# Schema_antenne.net
KiCad netlist of a schematic drawn in Altium Designer
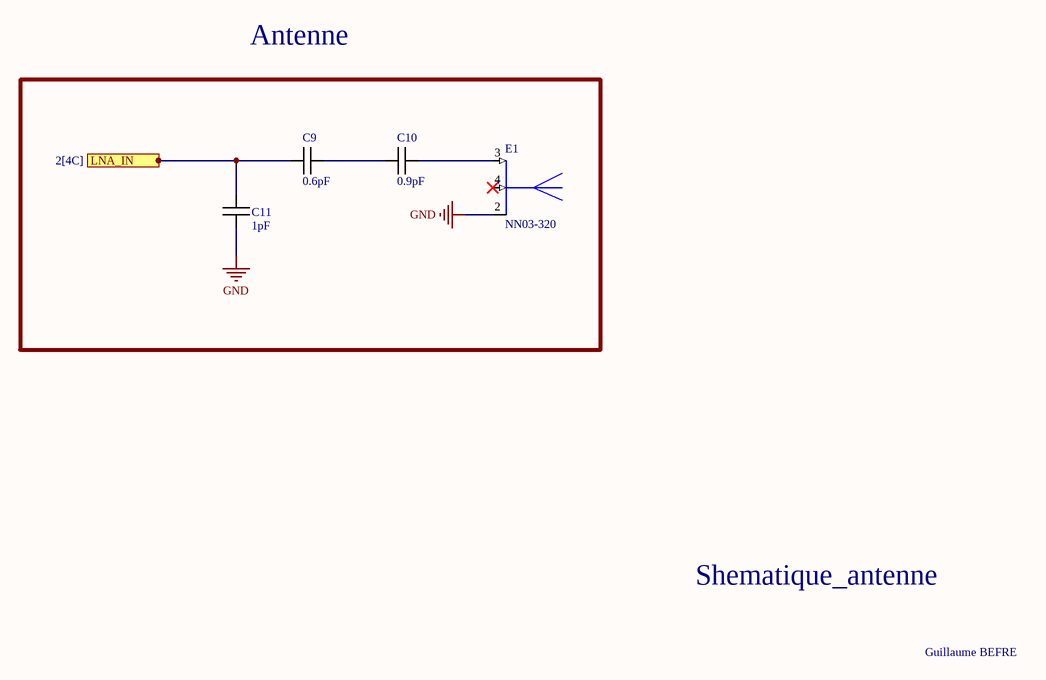
[diagram p0: Schema_antenne.SchDoc]

(export (version "E")
  (design (tool "Eeschema 10.0.6"))
  (components
    (comp (ref "C9")
      (value "0.6pF")
      (footprint "CAPC1005X06N")
      (libsource (lib "SCHLibrary") (part "Capacitor"))
    )
    (comp (ref "C10")
      (value "0.9pF")
      (footprint "CAPC1005X06N")
      (libsource (lib "SCHLibrary") (part "Capacitor"))
    )
    (comp (ref "C11")
      (value "1pF")
      (footprint "CAPC1005X06N")
      (libsource (lib "SCHLibrary") (part "Capacitor"))
    )
    (comp (ref "E1")
      (value "NN03-320")
      (footprint "XCVR_NN03-320")
      (fields (field (name "MOUSER PART NUMBER") "128-NN03-320"))
      (libsource (lib "SCHLibrary") (part "NN03-320"))
    )
  )
  (nets
    (net (code "1") (name "/LNA_IN") (class "Default")
      (node (ref "C11") (pin "1") (pinfunction "1_1") (pintype "passive"))
      (node (ref "C9") (pin "2") (pinfunction "2_2") (pintype "passive"))
    )
    (net (code "2") (name "GND") (class "Default")
      (node (ref "C11") (pin "2") (pinfunction "2_2") (pintype "passive"))
      (node (ref "E1") (pin "2") (pinfunction "GROUND_2") (pintype "power_in"))
    )
    (net (code "3") (name "Net-(C10-Pad2)") (class "Default")
      (node (ref "C10") (pin "2") (pinfunction "2_2") (pintype "passive"))
      (node (ref "C9") (pin "1") (pinfunction "1_1") (pintype "passive"))
    )
    (net (code "4") (name "Net-(E1-FEED_BLUETOOTH)") (class "Default")
      (node (ref "C10") (pin "1") (pinfunction "1_1") (pintype "passive"))
      (node (ref "E1") (pin "3") (pinfunction "FEED_BLUETOOTH_3") (pintype "input"))
    )
    (net (code "5") (name "unconnected-(E1-FEED_GNSS-Pad4)") (class "Default")
      (node (ref "E1") (pin "4") (pinfunction "FEED_GNSS_4") (pintype "input+no_connect"))
    )
  )
)
